# H3_MIDIController_Rev_2_PZBoard.net
KiCad netlist of a schematic drawn in EAGLE
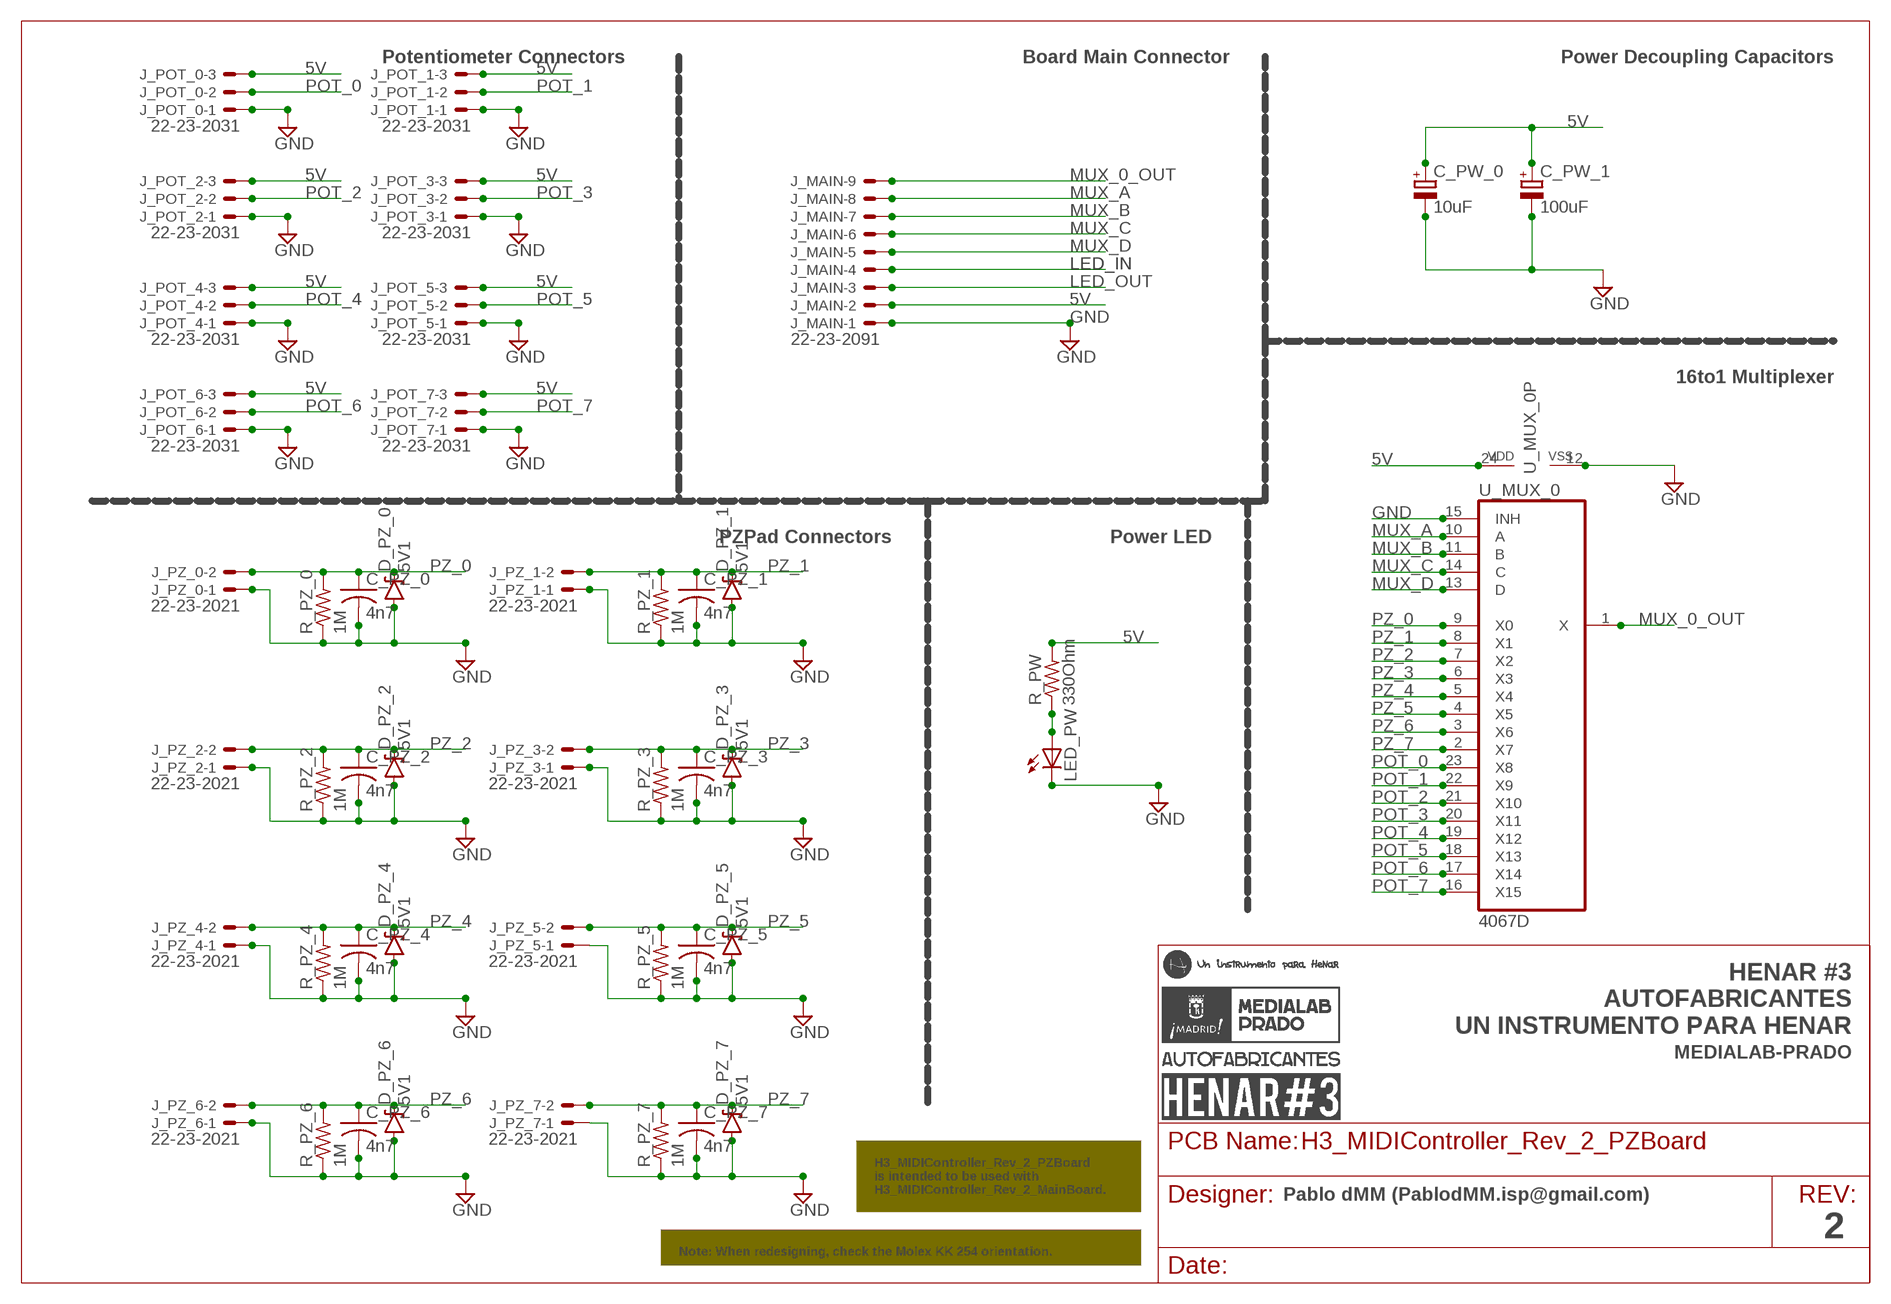
[diagram p0: schematic, sheet 1]

(export (version "E")
  (design (tool "Eeschema 10.0.6"))
  (components
    (comp (ref "C_PW_0")
      (value "10uF")
      (footprint "eagle-import:TT2D6L")
      (libsource (lib "eagle-import") (part "CPOL-EUTT2D6L"))
    )
    (comp (ref "C_PW_1")
      (value "100uF")
      (footprint "eagle-import:TT2D6L")
      (libsource (lib "eagle-import") (part "CPOL-EUTT2D6L"))
    )
    (comp (ref "C_PZ_0")
      (value "4n7")
      (footprint "eagle-import:C1206")
      (libsource (lib "eagle-import") (part "C-USC1206"))
    )
    (comp (ref "C_PZ_1")
      (value "4n7")
      (footprint "eagle-import:C1206")
      (libsource (lib "eagle-import") (part "C-USC1206"))
    )
    (comp (ref "C_PZ_2")
      (value "4n7")
      (footprint "eagle-import:C1206")
      (libsource (lib "eagle-import") (part "C-USC1206"))
    )
    (comp (ref "C_PZ_3")
      (value "4n7")
      (footprint "eagle-import:C1206")
      (libsource (lib "eagle-import") (part "C-USC1206"))
    )
    (comp (ref "C_PZ_4")
      (value "4n7")
      (footprint "eagle-import:C1206")
      (libsource (lib "eagle-import") (part "C-USC1206"))
    )
    (comp (ref "C_PZ_5")
      (value "4n7")
      (footprint "eagle-import:C1206")
      (libsource (lib "eagle-import") (part "C-USC1206"))
    )
    (comp (ref "C_PZ_6")
      (value "4n7")
      (footprint "eagle-import:C1206")
      (libsource (lib "eagle-import") (part "C-USC1206"))
    )
    (comp (ref "C_PZ_7")
      (value "4n7")
      (footprint "eagle-import:C1206")
      (libsource (lib "eagle-import") (part "C-USC1206"))
    )
    (comp (ref "D_PZ_0")
      (value "5V1")
      (footprint "eagle-import:DIODE-BZT52")
      (libsource (lib "eagle-import") (part "DIODE-ZENER"))
    )
    (comp (ref "D_PZ_1")
      (value "5V1")
      (footprint "eagle-import:DIODE-BZT52")
      (libsource (lib "eagle-import") (part "DIODE-ZENER"))
    )
    (comp (ref "D_PZ_2")
      (value "5V1")
      (footprint "eagle-import:DIODE-BZT52")
      (libsource (lib "eagle-import") (part "DIODE-ZENER"))
    )
    (comp (ref "D_PZ_3")
      (value "5V1")
      (footprint "eagle-import:DIODE-BZT52")
      (libsource (lib "eagle-import") (part "DIODE-ZENER"))
    )
    (comp (ref "D_PZ_4")
      (value "5V1")
      (footprint "eagle-import:DIODE-BZT52")
      (libsource (lib "eagle-import") (part "DIODE-ZENER"))
    )
    (comp (ref "D_PZ_5")
      (value "5V1")
      (footprint "eagle-import:DIODE-BZT52")
      (libsource (lib "eagle-import") (part "DIODE-ZENER"))
    )
    (comp (ref "D_PZ_6")
      (value "5V1")
      (footprint "eagle-import:DIODE-BZT52")
      (libsource (lib "eagle-import") (part "DIODE-ZENER"))
    )
    (comp (ref "D_PZ_7")
      (value "5V1")
      (footprint "eagle-import:DIODE-BZT52")
      (libsource (lib "eagle-import") (part "DIODE-ZENER"))
    )
    (comp (ref "J_MAIN")
      (value "22-23-2091")
      (footprint "eagle-import:22-23-2091")
      (fields (field (name "MF") "MOLEX"))
      (libsource (lib "eagle-import") (part "22-23-2091"))
    )
    (comp (ref "J_POT_0")
      (value "22-23-2031")
      (footprint "eagle-import:22-23-2031")
      (fields (field (name "MF") "MOLEX"))
      (libsource (lib "eagle-import") (part "22-23-2031"))
    )
    (comp (ref "J_POT_1")
      (value "22-23-2031")
      (footprint "eagle-import:22-23-2031")
      (fields (field (name "MF") "MOLEX"))
      (libsource (lib "eagle-import") (part "22-23-2031"))
    )
    (comp (ref "J_POT_2")
      (value "22-23-2031")
      (footprint "eagle-import:22-23-2031")
      (fields (field (name "MF") "MOLEX"))
      (libsource (lib "eagle-import") (part "22-23-2031"))
    )
    (comp (ref "J_POT_3")
      (value "22-23-2031")
      (footprint "eagle-import:22-23-2031")
      (fields (field (name "MF") "MOLEX"))
      (libsource (lib "eagle-import") (part "22-23-2031"))
    )
    (comp (ref "J_POT_4")
      (value "22-23-2031")
      (footprint "eagle-import:22-23-2031")
      (fields (field (name "MF") "MOLEX"))
      (libsource (lib "eagle-import") (part "22-23-2031"))
    )
    (comp (ref "J_POT_5")
      (value "22-23-2031")
      (footprint "eagle-import:22-23-2031")
      (fields (field (name "MF") "MOLEX"))
      (libsource (lib "eagle-import") (part "22-23-2031"))
    )
    (comp (ref "J_POT_6")
      (value "22-23-2031")
      (footprint "eagle-import:22-23-2031")
      (fields (field (name "MF") "MOLEX"))
      (libsource (lib "eagle-import") (part "22-23-2031"))
    )
    (comp (ref "J_POT_7")
      (value "22-23-2031")
      (footprint "eagle-import:22-23-2031")
      (fields (field (name "MF") "MOLEX"))
      (libsource (lib "eagle-import") (part "22-23-2031"))
    )
    (comp (ref "J_PZ_0")
      (value "22-23-2021")
      (footprint "eagle-import:22-23-2021")
      (fields (field (name "MF") "MOLEX"))
      (libsource (lib "eagle-import") (part "22-23-2021"))
    )
    (comp (ref "J_PZ_1")
      (value "22-23-2021")
      (footprint "eagle-import:22-23-2021")
      (fields (field (name "MF") "MOLEX"))
      (libsource (lib "eagle-import") (part "22-23-2021"))
    )
    (comp (ref "J_PZ_2")
      (value "22-23-2021")
      (footprint "eagle-import:22-23-2021")
      (fields (field (name "MF") "MOLEX"))
      (libsource (lib "eagle-import") (part "22-23-2021"))
    )
    (comp (ref "J_PZ_3")
      (value "22-23-2021")
      (footprint "eagle-import:22-23-2021")
      (fields (field (name "MF") "MOLEX"))
      (libsource (lib "eagle-import") (part "22-23-2021"))
    )
    (comp (ref "J_PZ_4")
      (value "22-23-2021")
      (footprint "eagle-import:22-23-2021")
      (fields (field (name "MF") "MOLEX"))
      (libsource (lib "eagle-import") (part "22-23-2021"))
    )
    (comp (ref "J_PZ_5")
      (value "22-23-2021")
      (footprint "eagle-import:22-23-2021")
      (fields (field (name "MF") "MOLEX"))
      (libsource (lib "eagle-import") (part "22-23-2021"))
    )
    (comp (ref "J_PZ_6")
      (value "22-23-2021")
      (footprint "eagle-import:22-23-2021")
      (fields (field (name "MF") "MOLEX"))
      (libsource (lib "eagle-import") (part "22-23-2021"))
    )
    (comp (ref "J_PZ_7")
      (value "22-23-2021")
      (footprint "eagle-import:22-23-2021")
      (fields (field (name "MF") "MOLEX"))
      (libsource (lib "eagle-import") (part "22-23-2021"))
    )
    (comp (ref "LED_PW")
      (value "LEDSMT1206")
      (footprint "eagle-import:1206")
      (libsource (lib "eagle-import") (part "LEDSMT1206"))
    )
    (comp (ref "R_PW")
      (value "330Ohm")
      (footprint "eagle-import:M1206")
      (libsource (lib "eagle-import") (part "R-US_M1206"))
    )
    (comp (ref "R_PZ_0")
      (value "1M")
      (footprint "eagle-import:M1206")
      (libsource (lib "eagle-import") (part "R-US_M1206"))
    )
    (comp (ref "R_PZ_1")
      (value "1M")
      (footprint "eagle-import:M1206")
      (libsource (lib "eagle-import") (part "R-US_M1206"))
    )
    (comp (ref "R_PZ_2")
      (value "1M")
      (footprint "eagle-import:M1206")
      (libsource (lib "eagle-import") (part "R-US_M1206"))
    )
    (comp (ref "R_PZ_3")
      (value "1M")
      (footprint "eagle-import:M1206")
      (libsource (lib "eagle-import") (part "R-US_M1206"))
    )
    (comp (ref "R_PZ_4")
      (value "1M")
      (footprint "eagle-import:M1206")
      (libsource (lib "eagle-import") (part "R-US_M1206"))
    )
    (comp (ref "R_PZ_5")
      (value "1M")
      (footprint "eagle-import:M1206")
      (libsource (lib "eagle-import") (part "R-US_M1206"))
    )
    (comp (ref "R_PZ_6")
      (value "1M")
      (footprint "eagle-import:M1206")
      (libsource (lib "eagle-import") (part "R-US_M1206"))
    )
    (comp (ref "R_PZ_7")
      (value "1M")
      (footprint "eagle-import:M1206")
      (libsource (lib "eagle-import") (part "R-US_M1206"))
    )
    (comp (ref "U_MUX_0")
      (value "4067D")
      (footprint "eagle-import:SO24W")
      (libsource (lib "eagle-import") (part "4067D"))
    )
  )
  (nets
    (net (code "1") (name "/5V") (class "Default")
      (node (ref "C_PW_0") (pin "+") (pinfunction "+_+") (pintype "passive"))
      (node (ref "C_PW_1") (pin "+") (pinfunction "+_+") (pintype "passive"))
      (node (ref "J_MAIN") (pin "2") (pinfunction "S_2") (pintype "passive"))
      (node (ref "J_POT_0") (pin "3") (pinfunction "S_3") (pintype "passive"))
      (node (ref "J_POT_1") (pin "3") (pinfunction "S_3") (pintype "passive"))
      (node (ref "J_POT_2") (pin "3") (pinfunction "S_3") (pintype "passive"))
      (node (ref "J_POT_3") (pin "3") (pinfunction "S_3") (pintype "passive"))
      (node (ref "J_POT_4") (pin "3") (pinfunction "S_3") (pintype "passive"))
      (node (ref "J_POT_5") (pin "3") (pinfunction "S_3") (pintype "passive"))
      (node (ref "J_POT_6") (pin "3") (pinfunction "S_3") (pintype "passive"))
      (node (ref "J_POT_7") (pin "3") (pinfunction "S_3") (pintype "passive"))
      (node (ref "R_PW") (pin "2") (pinfunction "2_2") (pintype "passive"))
      (node (ref "U_MUX_0") (pin "24") (pinfunction "VDD_24") (pintype "power_in"))
    )
    (net (code "2") (name "/LED_IN") (class "Default")
      (node (ref "J_MAIN") (pin "4") (pinfunction "S_4") (pintype "passive"))
    )
    (net (code "3") (name "/LED_OUT") (class "Default")
      (node (ref "J_MAIN") (pin "3") (pinfunction "S_3") (pintype "passive"))
    )
    (net (code "4") (name "/MUX_0_OUT") (class "Default")
      (node (ref "J_MAIN") (pin "9") (pinfunction "S_9") (pintype "passive"))
      (node (ref "U_MUX_0") (pin "1") (pinfunction "X_1") (pintype "output"))
    )
    (net (code "5") (name "/MUX_A") (class "Default")
      (node (ref "J_MAIN") (pin "8") (pinfunction "S_8") (pintype "passive"))
      (node (ref "U_MUX_0") (pin "10") (pinfunction "A_10") (pintype "input"))
    )
    (net (code "6") (name "/MUX_B") (class "Default")
      (node (ref "J_MAIN") (pin "7") (pinfunction "S_7") (pintype "passive"))
      (node (ref "U_MUX_0") (pin "11") (pinfunction "B_11") (pintype "input"))
    )
    (net (code "7") (name "/MUX_C") (class "Default")
      (node (ref "J_MAIN") (pin "6") (pinfunction "S_6") (pintype "passive"))
      (node (ref "U_MUX_0") (pin "14") (pinfunction "C_14") (pintype "input"))
    )
    (net (code "8") (name "/MUX_D") (class "Default")
      (node (ref "J_MAIN") (pin "5") (pinfunction "S_5") (pintype "passive"))
      (node (ref "U_MUX_0") (pin "13") (pinfunction "D_13") (pintype "input"))
    )
    (net (code "9") (name "/POT_0") (class "Default")
      (node (ref "J_POT_0") (pin "2") (pinfunction "S_2") (pintype "passive"))
      (node (ref "U_MUX_0") (pin "23") (pinfunction "X8_23") (pintype "input"))
    )
    (net (code "10") (name "/POT_1") (class "Default")
      (node (ref "J_POT_1") (pin "2") (pinfunction "S_2") (pintype "passive"))
      (node (ref "U_MUX_0") (pin "22") (pinfunction "X9_22") (pintype "input"))
    )
    (net (code "11") (name "/POT_2") (class "Default")
      (node (ref "J_POT_2") (pin "2") (pinfunction "S_2") (pintype "passive"))
      (node (ref "U_MUX_0") (pin "21") (pinfunction "X10_21") (pintype "input"))
    )
    (net (code "12") (name "/POT_3") (class "Default")
      (node (ref "J_POT_3") (pin "2") (pinfunction "S_2") (pintype "passive"))
      (node (ref "U_MUX_0") (pin "20") (pinfunction "X11_20") (pintype "input"))
    )
    (net (code "13") (name "/POT_4") (class "Default")
      (node (ref "J_POT_4") (pin "2") (pinfunction "S_2") (pintype "passive"))
      (node (ref "U_MUX_0") (pin "19") (pinfunction "X12_19") (pintype "input"))
    )
    (net (code "14") (name "/POT_5") (class "Default")
      (node (ref "J_POT_5") (pin "2") (pinfunction "S_2") (pintype "passive"))
      (node (ref "U_MUX_0") (pin "18") (pinfunction "X13_18") (pintype "input"))
    )
    (net (code "15") (name "/POT_6") (class "Default")
      (node (ref "J_POT_6") (pin "2") (pinfunction "S_2") (pintype "passive"))
      (node (ref "U_MUX_0") (pin "17") (pinfunction "X14_17") (pintype "input"))
    )
    (net (code "16") (name "/POT_7") (class "Default")
      (node (ref "J_POT_7") (pin "2") (pinfunction "S_2") (pintype "passive"))
      (node (ref "U_MUX_0") (pin "16") (pinfunction "X15_16") (pintype "input"))
    )
    (net (code "17") (name "/PZ_0") (class "Default")
      (node (ref "C_PZ_0") (pin "1") (pinfunction "1_1") (pintype "passive"))
      (node (ref "D_PZ_0") (pin "C") (pinfunction "C_C") (pintype "passive"))
      (node (ref "J_PZ_0") (pin "2") (pinfunction "S_2") (pintype "passive"))
      (node (ref "R_PZ_0") (pin "2") (pinfunction "2_2") (pintype "passive"))
      (node (ref "U_MUX_0") (pin "9") (pinfunction "X0_9") (pintype "input"))
    )
    (net (code "18") (name "/PZ_1") (class "Default")
      (node (ref "C_PZ_1") (pin "1") (pinfunction "1_1") (pintype "passive"))
      (node (ref "D_PZ_1") (pin "C") (pinfunction "C_C") (pintype "passive"))
      (node (ref "J_PZ_1") (pin "2") (pinfunction "S_2") (pintype "passive"))
      (node (ref "R_PZ_1") (pin "2") (pinfunction "2_2") (pintype "passive"))
      (node (ref "U_MUX_0") (pin "8") (pinfunction "X1_8") (pintype "input"))
    )
    (net (code "19") (name "/PZ_2") (class "Default")
      (node (ref "C_PZ_2") (pin "1") (pinfunction "1_1") (pintype "passive"))
      (node (ref "D_PZ_2") (pin "C") (pinfunction "C_C") (pintype "passive"))
      (node (ref "J_PZ_2") (pin "2") (pinfunction "S_2") (pintype "passive"))
      (node (ref "R_PZ_2") (pin "2") (pinfunction "2_2") (pintype "passive"))
      (node (ref "U_MUX_0") (pin "7") (pinfunction "X2_7") (pintype "input"))
    )
    (net (code "20") (name "/PZ_3") (class "Default")
      (node (ref "C_PZ_3") (pin "1") (pinfunction "1_1") (pintype "passive"))
      (node (ref "D_PZ_3") (pin "C") (pinfunction "C_C") (pintype "passive"))
      (node (ref "J_PZ_3") (pin "2") (pinfunction "S_2") (pintype "passive"))
      (node (ref "R_PZ_3") (pin "2") (pinfunction "2_2") (pintype "passive"))
      (node (ref "U_MUX_0") (pin "6") (pinfunction "X3_6") (pintype "input"))
    )
    (net (code "21") (name "/PZ_4") (class "Default")
      (node (ref "C_PZ_4") (pin "1") (pinfunction "1_1") (pintype "passive"))
      (node (ref "D_PZ_4") (pin "C") (pinfunction "C_C") (pintype "passive"))
      (node (ref "J_PZ_4") (pin "2") (pinfunction "S_2") (pintype "passive"))
      (node (ref "R_PZ_4") (pin "2") (pinfunction "2_2") (pintype "passive"))
      (node (ref "U_MUX_0") (pin "5") (pinfunction "X4_5") (pintype "input"))
    )
    (net (code "22") (name "/PZ_5") (class "Default")
      (node (ref "C_PZ_5") (pin "1") (pinfunction "1_1") (pintype "passive"))
      (node (ref "D_PZ_5") (pin "C") (pinfunction "C_C") (pintype "passive"))
      (node (ref "J_PZ_5") (pin "2") (pinfunction "S_2") (pintype "passive"))
      (node (ref "R_PZ_5") (pin "2") (pinfunction "2_2") (pintype "passive"))
      (node (ref "U_MUX_0") (pin "4") (pinfunction "X5_4") (pintype "input"))
    )
    (net (code "23") (name "/PZ_6") (class "Default")
      (node (ref "C_PZ_6") (pin "1") (pinfunction "1_1") (pintype "passive"))
      (node (ref "D_PZ_6") (pin "C") (pinfunction "C_C") (pintype "passive"))
      (node (ref "J_PZ_6") (pin "2") (pinfunction "S_2") (pintype "passive"))
      (node (ref "R_PZ_6") (pin "2") (pinfunction "2_2") (pintype "passive"))
      (node (ref "U_MUX_0") (pin "3") (pinfunction "X6_3") (pintype "input"))
    )
    (net (code "24") (name "/PZ_7") (class "Default")
      (node (ref "C_PZ_7") (pin "1") (pinfunction "1_1") (pintype "passive"))
      (node (ref "D_PZ_7") (pin "C") (pinfunction "C_C") (pintype "passive"))
      (node (ref "J_PZ_7") (pin "2") (pinfunction "S_2") (pintype "passive"))
      (node (ref "R_PZ_7") (pin "2") (pinfunction "2_2") (pintype "passive"))
      (node (ref "U_MUX_0") (pin "2") (pinfunction "X7_2") (pintype "input"))
    )
    (net (code "25") (name "GND") (class "Default")
      (node (ref "C_PW_0") (pin "-") (pinfunction "-_-") (pintype "passive"))
      (node (ref "C_PW_1") (pin "-") (pinfunction "-_-") (pintype "passive"))
      (node (ref "C_PZ_0") (pin "2") (pinfunction "2_2") (pintype "passive"))
      (node (ref "C_PZ_1") (pin "2") (pinfunction "2_2") (pintype "passive"))
      (node (ref "C_PZ_2") (pin "2") (pinfunction "2_2") (pintype "passive"))
      (node (ref "C_PZ_3") (pin "2") (pinfunction "2_2") (pintype "passive"))
      (node (ref "C_PZ_4") (pin "2") (pinfunction "2_2") (pintype "passive"))
      (node (ref "C_PZ_5") (pin "2") (pinfunction "2_2") (pintype "passive"))
      (node (ref "C_PZ_6") (pin "2") (pinfunction "2_2") (pintype "passive"))
      (node (ref "C_PZ_7") (pin "2") (pinfunction "2_2") (pintype "passive"))
      (node (ref "D_PZ_0") (pin "A") (pinfunction "A_A") (pintype "passive"))
      (node (ref "D_PZ_1") (pin "A") (pinfunction "A_A") (pintype "passive"))
      (node (ref "D_PZ_2") (pin "A") (pinfunction "A_A") (pintype "passive"))
      (node (ref "D_PZ_3") (pin "A") (pinfunction "A_A") (pintype "passive"))
      (node (ref "D_PZ_4") (pin "A") (pinfunction "A_A") (pintype "passive"))
      (node (ref "D_PZ_5") (pin "A") (pinfunction "A_A") (pintype "passive"))
      (node (ref "D_PZ_6") (pin "A") (pinfunction "A_A") (pintype "passive"))
      (node (ref "D_PZ_7") (pin "A") (pinfunction "A_A") (pintype "passive"))
      (node (ref "J_MAIN") (pin "1") (pinfunction "S_1") (pintype "passive"))
      (node (ref "J_POT_0") (pin "1") (pinfunction "S_1") (pintype "passive"))
      (node (ref "J_POT_1") (pin "1") (pinfunction "S_1") (pintype "passive"))
      (node (ref "J_POT_2") (pin "1") (pinfunction "S_1") (pintype "passive"))
      (node (ref "J_POT_3") (pin "1") (pinfunction "S_1") (pintype "passive"))
      (node (ref "J_POT_4") (pin "1") (pinfunction "S_1") (pintype "passive"))
      (node (ref "J_POT_5") (pin "1") (pinfunction "S_1") (pintype "passive"))
      (node (ref "J_POT_6") (pin "1") (pinfunction "S_1") (pintype "passive"))
      (node (ref "J_POT_7") (pin "1") (pinfunction "S_1") (pintype "passive"))
      (node (ref "J_PZ_0") (pin "1") (pinfunction "S_1") (pintype "passive"))
      (node (ref "J_PZ_1") (pin "1") (pinfunction "S_1") (pintype "passive"))
      (node (ref "J_PZ_2") (pin "1") (pinfunction "S_1") (pintype "passive"))
      (node (ref "J_PZ_3") (pin "1") (pinfunction "S_1") (pintype "passive"))
      (node (ref "J_PZ_4") (pin "1") (pinfunction "S_1") (pintype "passive"))
      (node (ref "J_PZ_5") (pin "1") (pinfunction "S_1") (pintype "passive"))
      (node (ref "J_PZ_6") (pin "1") (pinfunction "S_1") (pintype "passive"))
      (node (ref "J_PZ_7") (pin "1") (pinfunction "S_1") (pintype "passive"))
      (node (ref "LED_PW") (pin "C") (pinfunction "C_C") (pintype "passive"))
      (node (ref "R_PZ_0") (pin "1") (pinfunction "1_1") (pintype "passive"))
      (node (ref "R_PZ_1") (pin "1") (pinfunction "1_1") (pintype "passive"))
      (node (ref "R_PZ_2") (pin "1") (pinfunction "1_1") (pintype "passive"))
      (node (ref "R_PZ_3") (pin "1") (pinfunction "1_1") (pintype "passive"))
      (node (ref "R_PZ_4") (pin "1") (pinfunction "1_1") (pintype "passive"))
      (node (ref "R_PZ_5") (pin "1") (pinfunction "1_1") (pintype "passive"))
      (node (ref "R_PZ_6") (pin "1") (pinfunction "1_1") (pintype "passive"))
      (node (ref "R_PZ_7") (pin "1") (pinfunction "1_1") (pintype "passive"))
      (node (ref "U_MUX_0") (pin "12") (pinfunction "VSS_12") (pintype "power_in"))
      (node (ref "U_MUX_0") (pin "15") (pinfunction "INH_15") (pintype "input"))
    )
    (net (code "26") (name "Net-(LED_PW-PadA)") (class "Default")
      (node (ref "LED_PW") (pin "A") (pinfunction "A_A") (pintype "passive"))
      (node (ref "R_PW") (pin "1") (pinfunction "1_1") (pintype "passive"))
    )
  )
)
